# chaser.net
KiCad netlist of a schematic drawn in EasyEDA Pro
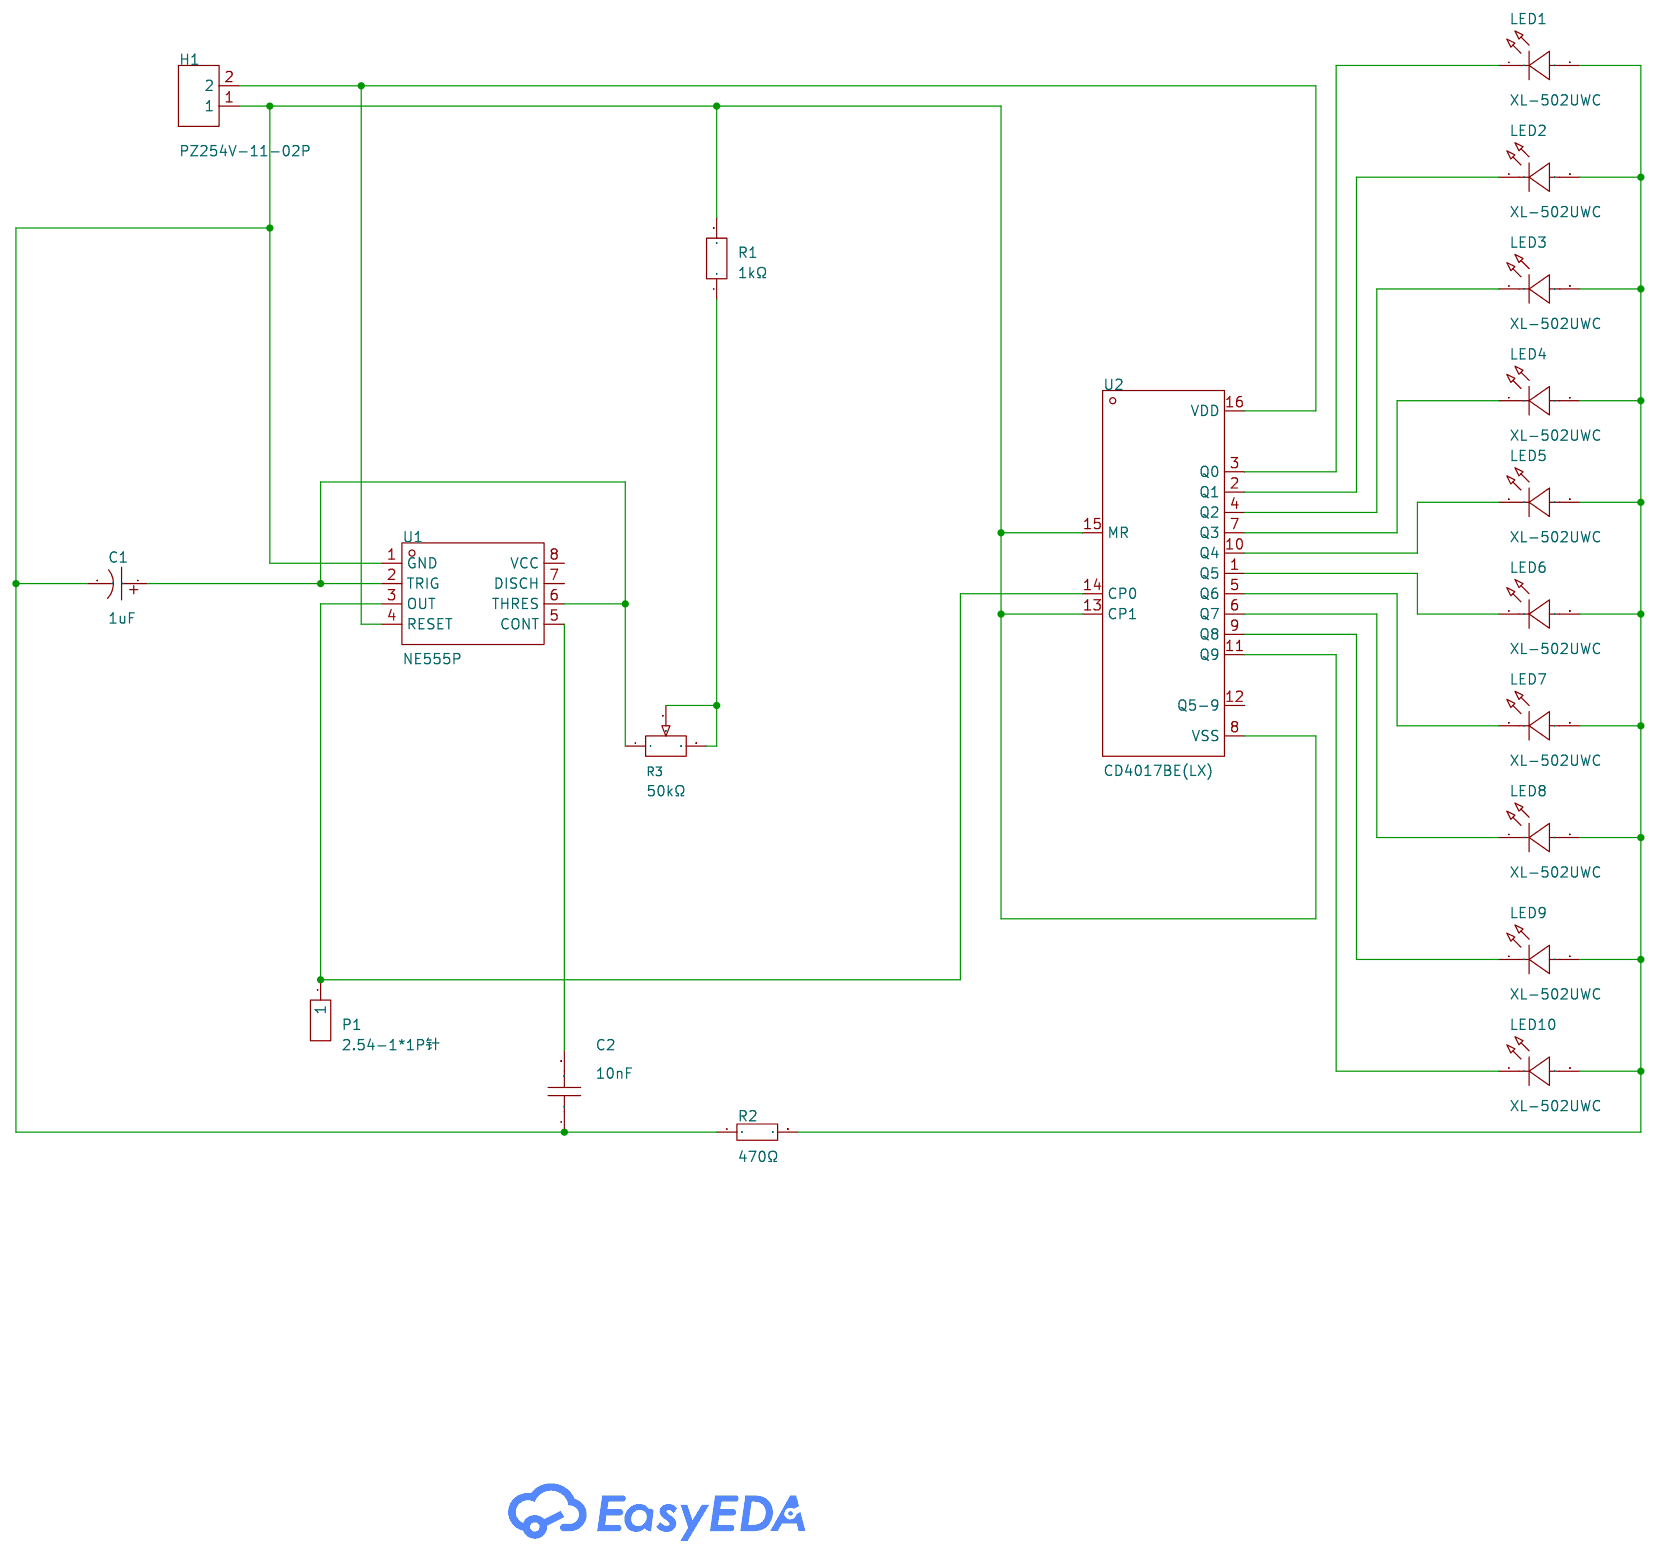
[diagram p0: schematic sheet]

(export (version "E")
  (design (tool "Eeschema 10.0.6"))
  (components
    (comp (ref "C1")
      (value "1uF")
      (footprint "easyedapro:CAP-TH_BD5.0-P2.00-D0.8-FD")
      (fields (field (name "Manufacturer Part") "KF010M050C110A") (field (name "Manufacturer") "CapXon(丰宾)"))
      (libsource (lib "easyedapro") (part "KF010M050C110A"))
    )
    (comp (ref "C2")
      (value "10nF")
      (footprint "easyedapro:CAP-TH_L8.0-W4.0-P5.00-D1.2")
      (fields (field (name "Manufacturer Part") "N09F1B103MN0B0S0N0") (field (name "Manufacturer") "STE(松田)"))
      (libsource (lib "easyedapro") (part "N09F1B103MN0B0S0N0"))
    )
    (comp (ref "H1")
      (value "PZ254V-11-02P")
      (footprint "easyedapro:HDR-TH_2P-P2.54-V-M")
      (fields (field (name "Manufacturer") "XFCN(兴飞)"))
      (libsource (lib "easyedapro") (part "PZ254V-11-02P"))
    )
    (comp (ref "LED1")
      (value "XL-502UWC")
      (footprint "easyedapro:LED-TH_BD5.9-P2.54-RD_WHITE")
      (fields (field (name "Manufacturer") "XINGLIGHT(成兴光)"))
      (libsource (lib "easyedapro") (part "XL-502UWC"))
    )
    (comp (ref "LED2")
      (value "XL-502UWC")
      (footprint "easyedapro:LED-TH_BD5.9-P2.54-RD_WHITE")
      (fields (field (name "Manufacturer") "XINGLIGHT(成兴光)"))
      (libsource (lib "easyedapro") (part "XL-502UWC"))
    )
    (comp (ref "LED3")
      (value "XL-502UWC")
      (footprint "easyedapro:LED-TH_BD5.9-P2.54-RD_WHITE")
      (fields (field (name "Manufacturer") "XINGLIGHT(成兴光)"))
      (libsource (lib "easyedapro") (part "XL-502UWC"))
    )
    (comp (ref "LED4")
      (value "XL-502UWC")
      (footprint "easyedapro:LED-TH_BD5.9-P2.54-RD_WHITE")
      (fields (field (name "Manufacturer") "XINGLIGHT(成兴光)"))
      (libsource (lib "easyedapro") (part "XL-502UWC"))
    )
    (comp (ref "LED5")
      (value "XL-502UWC")
      (footprint "easyedapro:LED-TH_BD5.9-P2.54-RD_WHITE")
      (fields (field (name "Manufacturer") "XINGLIGHT(成兴光)"))
      (libsource (lib "easyedapro") (part "XL-502UWC"))
    )
    (comp (ref "LED6")
      (value "XL-502UWC")
      (footprint "easyedapro:LED-TH_BD5.9-P2.54-RD_WHITE")
      (fields (field (name "Manufacturer") "XINGLIGHT(成兴光)"))
      (libsource (lib "easyedapro") (part "XL-502UWC"))
    )
    (comp (ref "LED7")
      (value "XL-502UWC")
      (footprint "easyedapro:LED-TH_BD5.9-P2.54-RD_WHITE")
      (fields (field (name "Manufacturer") "XINGLIGHT(成兴光)"))
      (libsource (lib "easyedapro") (part "XL-502UWC"))
    )
    (comp (ref "LED8")
      (value "XL-502UWC")
      (footprint "easyedapro:LED-TH_BD5.9-P2.54-RD_WHITE")
      (fields (field (name "Manufacturer") "XINGLIGHT(成兴光)"))
      (libsource (lib "easyedapro") (part "XL-502UWC"))
    )
    (comp (ref "LED9")
      (value "XL-502UWC")
      (footprint "easyedapro:LED-TH_BD5.9-P2.54-RD_WHITE")
      (fields (field (name "Manufacturer") "XINGLIGHT(成兴光)"))
      (libsource (lib "easyedapro") (part "XL-502UWC"))
    )
    (comp (ref "LED10")
      (value "XL-502UWC")
      (footprint "easyedapro:LED-TH_BD5.9-P2.54-RD_WHITE")
      (fields (field (name "Manufacturer") "XINGLIGHT(成兴光)"))
      (libsource (lib "easyedapro") (part "XL-502UWC"))
    )
    (comp (ref "P1")
      (value "2.54-1*1P针")
      (footprint "easyedapro:HDR-TH_1P-P2.54-V-M")
      (fields (field (name "Manufacturer") "BOOMELE(博穆精密)"))
      (libsource (lib "easyedapro") (part "Header-Male-2.54_1x1"))
    )
    (comp (ref "R1")
      (value "1kΩ")
      (footprint "easyedapro:RES-TH_BD2.3-L6.5-P10.50-D0.5")
      (fields (field (name "Manufacturer Part") "MF1/4W-1KΩ±1%T52") (field (name "Manufacturer") "华星机电"))
      (libsource (lib "easyedapro") (part "MF1/4W-1KΩ±1%T52"))
    )
    (comp (ref "R2")
      (value "470Ω")
      (footprint "easyedapro:RES-TH_BD2.2-L6.5-P10.50-D0.6")
      (fields
        (field (name "Manufacturer Part") "MFR0W4F4700A50")
        (field (name "Manufacturer") "UNI-ROYAL(厚声)")
      )
      (libsource (lib "easyedapro") (part "MFR0W4F4700A50"))
    )
    (comp (ref "R3")
      (value "50kΩ")
      (footprint "easyedapro:RES-ADJ-TH_3P-L9.5-W4.85-P2.50-BL-L")
      (fields (field (name "Manufacturer Part") "3296X-1-503") (field (name "Manufacturer") "BOCHEN(博晨)"))
      (libsource (lib "easyedapro") (part "3296X-1-503_C118912"))
    )
    (comp (ref "U1")
      (value "NE555P")
      (footprint "easyedapro:DIP-8_L9.8-W6.6-P2.54-LS7.6-BL")
      (fields (field (name "Manufacturer") "TI(德州仪器)"))
      (libsource (lib "easyedapro") (part "NE555P"))
    )
    (comp (ref "U2")
      (value "CD4017BE(LX)")
      (footprint "easyedapro:PDIP-16_L19.3-W6.4-P2.54-LS7.94-BL")
      (fields (field (name "Manufacturer") "LX(灵星芯微)"))
      (libsource (lib "easyedapro") (part "CD4017BE(LX)"))
    )
  )
  (nets
    (net (code "1") (name "Net-(LED1-A)") (class "Default")
      (node (ref "LED1") (pin "2") (pinfunction "A_2") (pintype "unspecified"))
      (node (ref "LED10") (pin "2") (pinfunction "A_2") (pintype "unspecified"))
      (node (ref "LED2") (pin "2") (pinfunction "A_2") (pintype "unspecified"))
      (node (ref "LED3") (pin "2") (pinfunction "A_2") (pintype "unspecified"))
      (node (ref "LED4") (pin "2") (pinfunction "A_2") (pintype "unspecified"))
      (node (ref "LED5") (pin "2") (pinfunction "A_2") (pintype "unspecified"))
      (node (ref "LED6") (pin "2") (pinfunction "A_2") (pintype "unspecified"))
      (node (ref "LED7") (pin "2") (pinfunction "A_2") (pintype "unspecified"))
      (node (ref "LED8") (pin "2") (pinfunction "A_2") (pintype "unspecified"))
      (node (ref "LED9") (pin "2") (pinfunction "A_2") (pintype "unspecified"))
      (node (ref "R2") (pin "2") (pinfunction "2_2") (pintype "input"))
    )
    (net (code "2") (name "Net-(LED1-K)") (class "Default")
      (node (ref "LED1") (pin "1") (pinfunction "K_1") (pintype "unspecified"))
      (node (ref "U2") (pin "3") (pinfunction "Q0_3") (pintype "unspecified"))
    )
    (net (code "3") (name "Net-(LED2-K)") (class "Default")
      (node (ref "LED2") (pin "1") (pinfunction "K_1") (pintype "unspecified"))
      (node (ref "U2") (pin "2") (pinfunction "Q1_2") (pintype "unspecified"))
    )
    (net (code "4") (name "Net-(LED3-K)") (class "Default")
      (node (ref "LED3") (pin "1") (pinfunction "K_1") (pintype "unspecified"))
      (node (ref "U2") (pin "4") (pinfunction "Q2_4") (pintype "unspecified"))
    )
    (net (code "5") (name "Net-(LED4-K)") (class "Default")
      (node (ref "LED4") (pin "1") (pinfunction "K_1") (pintype "unspecified"))
      (node (ref "U2") (pin "7") (pinfunction "Q3_7") (pintype "unspecified"))
    )
    (net (code "6") (name "Net-(LED5-K)") (class "Default")
      (node (ref "LED5") (pin "1") (pinfunction "K_1") (pintype "unspecified"))
      (node (ref "U2") (pin "10") (pinfunction "Q4_10") (pintype "unspecified"))
    )
    (net (code "7") (name "Net-(LED6-K)") (class "Default")
      (node (ref "LED6") (pin "1") (pinfunction "K_1") (pintype "unspecified"))
      (node (ref "U2") (pin "1") (pinfunction "Q5_1") (pintype "unspecified"))
    )
    (net (code "8") (name "Net-(LED7-K)") (class "Default")
      (node (ref "LED7") (pin "1") (pinfunction "K_1") (pintype "unspecified"))
      (node (ref "U2") (pin "5") (pinfunction "Q6_5") (pintype "unspecified"))
    )
    (net (code "9") (name "Net-(LED8-K)") (class "Default")
      (node (ref "LED8") (pin "1") (pinfunction "K_1") (pintype "unspecified"))
      (node (ref "U2") (pin "6") (pinfunction "Q7_6") (pintype "unspecified"))
    )
    (net (code "10") (name "Net-(LED9-K)") (class "Default")
      (node (ref "LED9") (pin "1") (pinfunction "K_1") (pintype "unspecified"))
      (node (ref "U2") (pin "9") (pinfunction "Q8_9") (pintype "unspecified"))
    )
    (net (code "11") (name "Net-(LED10-K)") (class "Default")
      (node (ref "LED10") (pin "1") (pinfunction "K_1") (pintype "unspecified"))
      (node (ref "U2") (pin "11") (pinfunction "Q9_11") (pintype "unspecified"))
    )
    (net (code "12") (name "Net-(R1-Pad1)") (class "Default")
      (node (ref "R1") (pin "1") (pinfunction "1_1") (pintype "unspecified"))
      (node (ref "R3") (pin "2") (pinfunction "2_2") (pintype "input"))
      (node (ref "R3") (pin "3") (pinfunction "3_3") (pintype "input"))
    )
    (net (code "13") (name "Net-(U1-CONT)") (class "Default")
      (node (ref "C2") (pin "2") (pinfunction "2_2") (pintype "unspecified"))
      (node (ref "U1") (pin "5") (pinfunction "CONT_5") (pintype "input"))
    )
    (net (code "14") (name "Net-(U1-GND)") (class "Default")
      (node (ref "C1") (pin "2") (pinfunction "2_2") (pintype "input"))
      (node (ref "C2") (pin "1") (pinfunction "1_1") (pintype "unspecified"))
      (node (ref "H1") (pin "1") (pinfunction "1_1") (pintype "unspecified"))
      (node (ref "R1") (pin "2") (pinfunction "2_2") (pintype "unspecified"))
      (node (ref "R2") (pin "1") (pinfunction "1_1") (pintype "input"))
      (node (ref "U1") (pin "1") (pinfunction "GND_1") (pintype "input"))
      (node (ref "U2") (pin "13") (pinfunction "CP1_13") (pintype "unspecified"))
      (node (ref "U2") (pin "15") (pinfunction "MR_15") (pintype "unspecified"))
      (node (ref "U2") (pin "8") (pinfunction "VSS_8") (pintype "unspecified"))
    )
    (net (code "15") (name "Net-(U1-OUT)") (class "Default")
      (node (ref "P1") (pin "1") (pinfunction "1_1") (pintype "input"))
      (node (ref "U1") (pin "3") (pinfunction "OUT_3") (pintype "input"))
      (node (ref "U2") (pin "14") (pinfunction "CP0_14") (pintype "unspecified"))
    )
    (net (code "16") (name "Net-(U1-RESET)") (class "Default")
      (node (ref "H1") (pin "2") (pinfunction "2_2") (pintype "unspecified"))
      (node (ref "U1") (pin "4") (pinfunction "RESET_4") (pintype "input"))
      (node (ref "U2") (pin "16") (pinfunction "VDD_16") (pintype "unspecified"))
    )
    (net (code "17") (name "Net-(U1-THRES)") (class "Default")
      (node (ref "C1") (pin "1") (pinfunction "1_1") (pintype "input"))
      (node (ref "R3") (pin "1") (pinfunction "1_1") (pintype "input"))
      (node (ref "U1") (pin "2") (pinfunction "TRIG_2") (pintype "input"))
      (node (ref "U1") (pin "6") (pinfunction "THRES_6") (pintype "input"))
    )
    (net (code "18") (name "unconnected-(U1-DISCH-Pad7)") (class "Default")
      (node (ref "U1") (pin "7") (pinfunction "DISCH_7") (pintype "input"))
    )
    (net (code "19") (name "unconnected-(U1-VCC-Pad8)") (class "Default")
      (node (ref "U1") (pin "8") (pinfunction "VCC_8") (pintype "input"))
    )
    (net (code "20") (name "unconnected-(U2-Q5-9-Pad12)") (class "Default")
      (node (ref "U2") (pin "12") (pinfunction "Q5-9_12") (pintype "unspecified"))
    )
  )
)
